# main.net
KiCad netlist of a schematic drawn in Altium Designer
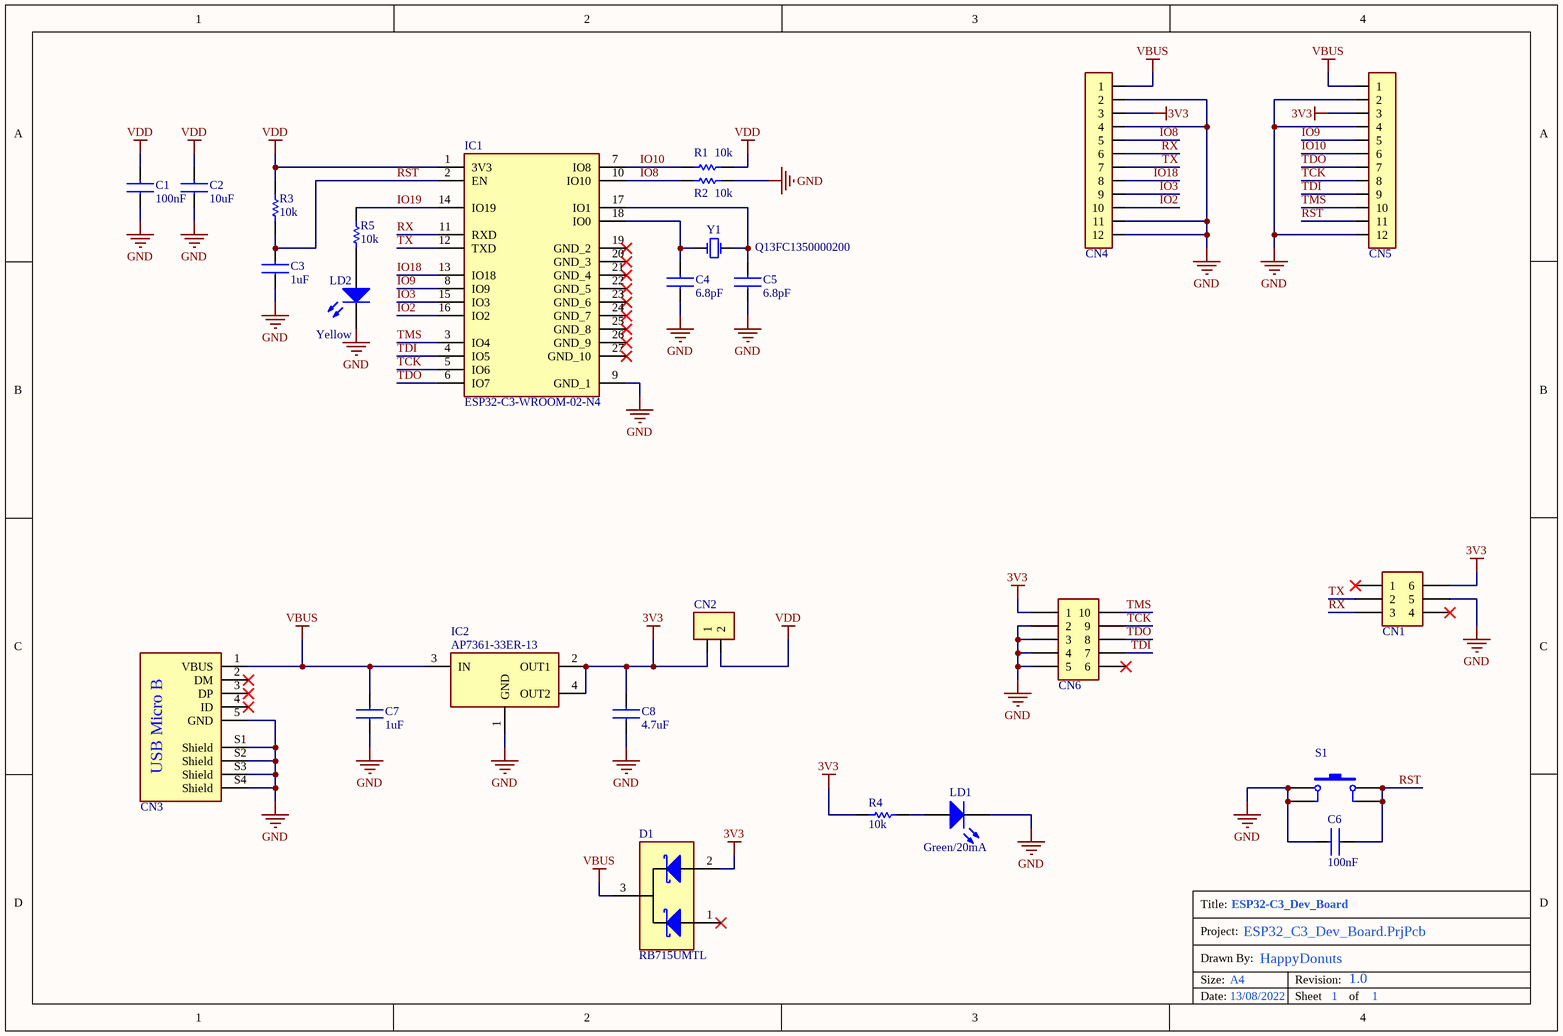
[diagram p0: main.SchDoc]

(export (version "E")
  (design (tool "Eeschema 10.0.6"))
  (components
    (comp (ref "C1")
      (value "100nF")
      (footprint "PcbLib1:CAPC2012X94N")
      (description "Capacitor")
      (fields
        (field (name "MANUFACTURER_PART_NUMBER") "CL21B104KBCNNNC")
        (field (name "MOUSER PART NUMBER") "187-CL21B104KBCNNNC")
      )
      (libsource (lib "Schlib1") (part "CL21B104KBCNNNC"))
    )
    (comp (ref "C2")
      (value "10uF")
      (footprint "PcbLib1:CAPC2012X135N")
      (description "Capacitor")
      (fields
        (field (name "MANUFACTURER_PART_NUMBER") "CL21A106MQFNNNE")
        (field (name "MOUSER PART NUMBER") "187-CL21A106MQFNNNE")
      )
      (libsource (lib "Schlib1") (part "CL21A106MQFNNNE"))
    )
    (comp (ref "C3")
      (value "1uF")
      (footprint "PcbLib1:CAPC2012X135N")
      (description "Capacitor")
      (fields
        (field (name "MANUFACTURER_PART_NUMBER") "CL21B105KBFNNNE")
        (field (name "MOUSER PART NUMBER") "187-CL21B105KBFNNNE")
      )
      (libsource (lib "Schlib1") (part "CL21B105KBFNNNE"))
    )
    (comp (ref "C4")
      (value "6.8pF")
      (footprint "PcbLib1:CAPC2012X94N")
      (description "Capacitor")
      (fields
        (field (name "MANUFACTURER_PART_NUMBER") "CC0805CRNPO9BN6R8")
        (field (name "MOUSER PART NUMBER") "603-CC805CRNPO9BN6R8")
      )
      (libsource (lib "Schlib1") (part "CC0805CRNPO9BN6R8"))
    )
    (comp (ref "C5")
      (value "6.8pF")
      (footprint "PcbLib1:CAPC2012X94N")
      (description "Capacitor")
      (fields
        (field (name "MANUFACTURER_PART_NUMBER") "CC0805CRNPO9BN6R8")
        (field (name "MOUSER PART NUMBER") "603-CC805CRNPO9BN6R8")
      )
      (libsource (lib "Schlib1") (part "CC0805CRNPO9BN6R8"))
    )
    (comp (ref "C6")
      (value "100nF")
      (footprint "PcbLib1:CAPC2012X94N")
      (description "Capacitor")
      (fields
        (field (name "MANUFACTURER_PART_NUMBER") "CL21B104KBCNNNC")
        (field (name "MOUSER PART NUMBER") "187-CL21B104KBCNNNC")
      )
      (libsource (lib "Schlib1") (part "CL21B104KBCNNNC"))
    )
    (comp (ref "C7")
      (value "1uF")
      (footprint "PcbLib1:CAPC2012X135N")
      (description "Capacitor")
      (fields
        (field (name "MANUFACTURER_PART_NUMBER") "CL21B105KBFNNNE")
        (field (name "MOUSER PART NUMBER") "187-CL21B105KBFNNNE")
      )
      (libsource (lib "Schlib1") (part "CL21B105KBFNNNE"))
    )
    (comp (ref "C8")
      (value "4.7uF")
      (footprint "PcbLib1:CAPC2012X135N")
      (description "Capacitor")
      (fields
        (field (name "MANUFACTURER_PART_NUMBER") "CL21A475KBQNNNE")
        (field (name "MOUSER PART NUMBER") "187-CL21A475KBQNNNE")
      )
      (libsource (lib "Schlib1") (part "CL21A475KBQNNNE"))
    )
    (comp (ref "CN1")
      (value "CN_2X3_1.27_BOX_1")
      (footprint "PcbLib1:CN_2X3_1.27_BOX_TH")
      (description "Connector")
      (libsource (lib "Schlib1") (part "CN_2X3_1.27_BOX_1"))
    )
    (comp (ref "CN2")
      (value "CN_2PIN")
      (footprint "PcbLib1:CN_2PIN")
      (description "Connector")
      (libsource (lib "Schlib1") (part "CN_2PIN"))
    )
    (comp (ref "CN3")
      (value "USB_B_AE")
      (footprint "PcbLib1:USB_B_AE")
      (description "USB connector")
      (libsource (lib "Schlib1") (part "USB_B_AE"))
    )
    (comp (ref "CN4")
      (value "CN_12PIN")
      (footprint "PcbLib1:CN_12PIN")
      (description "Connector")
      (libsource (lib "Schlib1") (part "CN_12PIN"))
    )
    (comp (ref "CN5")
      (value "CN_12PIN")
      (footprint "PcbLib1:CN_12PIN")
      (description "Connector")
      (libsource (lib "") (part "CN_12PIN_1"))
    )
    (comp (ref "CN6")
      (value "CN_2X5_1.27_BOX")
      (footprint "PcbLib1:CN_2X5_1.27_BOX_TH")
      (description "Connector")
      (libsource (lib "Schlib1") (part "CN_2X5_1.27_BOX"))
    )
    (comp (ref "D1")
      (value "RB715UMTL")
      (footprint "PcbLib1:DAN217UMTL")
      (description "Schottky Diode")
      (fields (field (name "MOUSER PART NUMBER") "755-RB715UMTL"))
      (libsource (lib "Schlib1") (part "RB715UMTL"))
    )
    (comp (ref "IC1")
      (value "ESP32-C3-WROOM-02-N4")
      (footprint "PcbLib1:ESP32C3WROOM02N4")
      (description "Integrated Circuit")
      (fields (field (name "MOUSER PART NUMBER") "356-ESP32C3WROOM02N4"))
      (libsource (lib "Schlib1") (part "ESP32-C3-WROOM-02-N4"))
    )
    (comp (ref "IC2")
      (value "AP7361-33ER-13")
      (footprint "PcbLib1:SOT230P700X180-4N")
      (description "LDO")
      (fields (field (name "MOUSER PART NUMBER") "621-AP7361-33ER-13"))
      (libsource (lib "Schlib1") (part "AP7361-33ER-13"))
    )
    (comp (ref "LD1")
      (value "Green/20mA")
      (footprint "PcbLib1:LEDC2012X85N_G")
      (description "LED")
      (fields
        (field (name "MANUFACTURER_PART_NUMBER") "LTST-C171KGKT")
        (field (name "MOUSER PART NUMBER") "859-LTST-C171KGKT")
      )
      (libsource (lib "Schlib1") (part "LTST-C171KGKT"))
    )
    (comp (ref "LD2")
      (value "Yellow")
      (footprint "PcbLib1:LEDC2012X85N_Y")
      (description "LED")
      (fields
        (field (name "MANUFACTURER_PART_NUMBER") "LTST-C171KSKT")
        (field (name "MOUSER PART NUMBER") "859-LTST-C171KSKT")
      )
      (libsource (lib "Schlib1") (part "LTST-C171KSKT"))
    )
    (comp (ref "R1")
      (value "10k")
      (footprint "PcbLib1:RESC2012X60N")
      (description "Resistor")
      (fields
        (field (name "MANUFACTURER_PART_NUMBER") "RC0805FR-0710KL")
        (field (name "MOUSER PART NUMBER") "603-RC0805FR-0710KL")
      )
      (libsource (lib "Schlib1") (part "RC0805FR-0710KL"))
    )
    (comp (ref "R2")
      (value "10k")
      (footprint "PcbLib1:RESC2012X60N")
      (description "Resistor")
      (fields
        (field (name "MANUFACTURER_PART_NUMBER") "RC0805FR-0710KL")
        (field (name "MOUSER PART NUMBER") "603-RC0805FR-0710KL")
      )
      (libsource (lib "Schlib1") (part "RC0805FR-0710KL"))
    )
    (comp (ref "R3")
      (value "10k")
      (footprint "PcbLib1:RESC2012X60N")
      (description "Resistor")
      (fields
        (field (name "MANUFACTURER_PART_NUMBER") "RC0805FR-0710KL")
        (field (name "MOUSER PART NUMBER") "603-RC0805FR-0710KL")
      )
      (libsource (lib "Schlib1") (part "RC0805FR-0710KL"))
    )
    (comp (ref "R4")
      (value "10k")
      (footprint "PcbLib1:RESC2012X60N")
      (description "Resistor")
      (fields
        (field (name "MANUFACTURER_PART_NUMBER") "RC0805FR-0710KL")
        (field (name "MOUSER PART NUMBER") "603-RC0805FR-0710KL")
      )
      (libsource (lib "Schlib1") (part "RC0805FR-0710KL"))
    )
    (comp (ref "R5")
      (value "10k")
      (footprint "PcbLib1:RESC2012X60N")
      (description "Resistor")
      (fields
        (field (name "MANUFACTURER_PART_NUMBER") "RC0805FR-0710KL")
        (field (name "MOUSER PART NUMBER") "603-RC0805FR-0710KL")
      )
      (libsource (lib "Schlib1") (part "RC0805FR-0710KL"))
    )
    (comp (ref "S1")
      (value "SKRPABE010")
      (footprint "PcbLib1:PTS815SJM250SMTRLFS")
      (description "Switch")
      (fields (field (name "MOUSER PART NUMBER") "688-SKRPAB"))
      (libsource (lib "Schlib1") (part "SKRPABE010"))
    )
    (comp (ref "Y1")
      (value "Q13FC1350000200")
      (footprint "PcbLib1:Q13FC1350000200")
      (description "Crystal")
      (libsource (lib "Schlib1") (part "Q13FC1350000200"))
    )
  )
  (nets
    (net (code "1") (name "/IO2") (class "Default")
      (node (ref "CN4") (pin "10") (pinfunction "10_10") (pintype "passive"))
      (node (ref "IC1") (pin "16") (pinfunction "IO2_16") (pintype "passive"))
    )
    (net (code "2") (name "/IO3") (class "Default")
      (node (ref "CN4") (pin "9") (pinfunction "9_9") (pintype "passive"))
      (node (ref "IC1") (pin "15") (pinfunction "IO3_15") (pintype "passive"))
    )
    (net (code "3") (name "/IO8") (class "Default")
      (node (ref "CN4") (pin "5") (pinfunction "5_5") (pintype "passive"))
      (node (ref "IC1") (pin "10") (pinfunction "IO10_10") (pintype "passive"))
      (node (ref "R2") (pin "1") (pinfunction "1_1") (pintype "passive"))
    )
    (net (code "4") (name "/IO9") (class "Default")
      (node (ref "CN5") (pin "5") (pinfunction "5_5") (pintype "passive"))
      (node (ref "IC1") (pin "8") (pinfunction "IO9_8") (pintype "passive"))
    )
    (net (code "5") (name "/IO10") (class "Default")
      (node (ref "CN5") (pin "6") (pinfunction "6_6") (pintype "passive"))
      (node (ref "IC1") (pin "7") (pinfunction "IO8_7") (pintype "passive"))
      (node (ref "R1") (pin "2") (pinfunction "2_2") (pintype "passive"))
    )
    (net (code "6") (name "/IO18") (class "Default")
      (node (ref "CN4") (pin "8") (pinfunction "8_8") (pintype "passive"))
      (node (ref "IC1") (pin "13") (pinfunction "IO18_13") (pintype "passive"))
    )
    (net (code "7") (name "/IO19") (class "Default")
      (node (ref "IC1") (pin "14") (pinfunction "IO19_14") (pintype "passive"))
      (node (ref "R5") (pin "2") (pinfunction "2_2") (pintype "passive"))
    )
    (net (code "8") (name "/RST") (class "Default")
      (node (ref "C3") (pin "2") (pinfunction "2_2") (pintype "passive"))
      (node (ref "C6") (pin "2") (pinfunction "2_2") (pintype "passive"))
      (node (ref "CN5") (pin "11") (pinfunction "11_11") (pintype "passive"))
      (node (ref "IC1") (pin "2") (pinfunction "EN_2") (pintype "passive"))
      (node (ref "R3") (pin "1") (pinfunction "1_1") (pintype "passive"))
      (node (ref "S1") (pin "3") (pinfunction "3_3") (pintype "passive"))
      (node (ref "S1") (pin "4") (pinfunction "4_4") (pintype "passive"))
    )
    (net (code "9") (name "/RX") (class "Default")
      (node (ref "CN1") (pin "3") (pinfunction "3_3") (pintype "passive"))
      (node (ref "CN4") (pin "6") (pinfunction "6_6") (pintype "passive"))
      (node (ref "IC1") (pin "11") (pinfunction "RXD_11") (pintype "passive"))
    )
    (net (code "10") (name "/TCK") (class "Default")
      (node (ref "CN5") (pin "8") (pinfunction "8_8") (pintype "passive"))
      (node (ref "CN6") (pin "9") (pinfunction "9_9") (pintype "passive"))
      (node (ref "IC1") (pin "5") (pinfunction "IO6_5") (pintype "passive"))
    )
    (net (code "11") (name "/TDI") (class "Default")
      (node (ref "CN5") (pin "9") (pinfunction "9_9") (pintype "passive"))
      (node (ref "CN6") (pin "7") (pinfunction "7_7") (pintype "passive"))
      (node (ref "IC1") (pin "4") (pinfunction "IO5_4") (pintype "passive"))
    )
    (net (code "12") (name "/TDO") (class "Default")
      (node (ref "CN5") (pin "7") (pinfunction "7_7") (pintype "passive"))
      (node (ref "CN6") (pin "8") (pinfunction "8_8") (pintype "passive"))
      (node (ref "IC1") (pin "6") (pinfunction "IO7_6") (pintype "passive"))
    )
    (net (code "13") (name "/TMS") (class "Default")
      (node (ref "CN5") (pin "10") (pinfunction "10_10") (pintype "passive"))
      (node (ref "CN6") (pin "10") (pinfunction "10_10") (pintype "passive"))
      (node (ref "IC1") (pin "3") (pinfunction "IO4_3") (pintype "passive"))
    )
    (net (code "14") (name "/TX") (class "Default")
      (node (ref "CN1") (pin "2") (pinfunction "2_2") (pintype "passive"))
      (node (ref "CN4") (pin "7") (pinfunction "7_7") (pintype "passive"))
      (node (ref "IC1") (pin "12") (pinfunction "TXD_12") (pintype "passive"))
    )
    (net (code "15") (name "3V3") (class "Default")
      (node (ref "C8") (pin "2") (pinfunction "2_2") (pintype "passive"))
      (node (ref "CN1") (pin "6") (pinfunction "6_6") (pintype "passive"))
      (node (ref "CN2") (pin "1") (pinfunction "1_1") (pintype "passive"))
      (node (ref "CN4") (pin "3") (pinfunction "3_3") (pintype "passive"))
      (node (ref "CN5") (pin "3") (pinfunction "3_3") (pintype "passive"))
      (node (ref "CN6") (pin "1") (pinfunction "1_1") (pintype "passive"))
      (node (ref "D1") (pin "2") (pinfunction "K_2_2") (pintype "passive"))
      (node (ref "IC2") (pin "2") (pinfunction "OUT1_2") (pintype "passive"))
      (node (ref "IC2") (pin "4") (pinfunction "OUT2_4") (pintype "passive"))
      (node (ref "R4") (pin "1") (pinfunction "1_1") (pintype "passive"))
    )
    (net (code "16") (name "GND") (class "Default")
      (node (ref "C1") (pin "1") (pinfunction "1_1") (pintype "passive"))
      (node (ref "C2") (pin "1") (pinfunction "1_1") (pintype "passive"))
      (node (ref "C3") (pin "1") (pinfunction "1_1") (pintype "passive"))
      (node (ref "C4") (pin "1") (pinfunction "1_1") (pintype "passive"))
      (node (ref "C5") (pin "1") (pinfunction "1_1") (pintype "passive"))
      (node (ref "C6") (pin "1") (pinfunction "1_1") (pintype "passive"))
      (node (ref "C7") (pin "1") (pinfunction "1_1") (pintype "passive"))
      (node (ref "C8") (pin "1") (pinfunction "1_1") (pintype "passive"))
      (node (ref "CN1") (pin "5") (pinfunction "5_5") (pintype "passive"))
      (node (ref "CN3") (pin "5") (pinfunction "GND_5") (pintype "passive"))
      (node (ref "CN3") (pin "S1") (pinfunction "Shield_S1") (pintype "passive"))
      (node (ref "CN3") (pin "S2") (pinfunction "Shield_S2") (pintype "passive"))
      (node (ref "CN3") (pin "S3") (pinfunction "Shield_S3") (pintype "passive"))
      (node (ref "CN3") (pin "S4") (pinfunction "Shield_S4") (pintype "passive"))
      (node (ref "CN4") (pin "11") (pinfunction "11_11") (pintype "passive"))
      (node (ref "CN4") (pin "12") (pinfunction "12_12") (pintype "passive"))
      (node (ref "CN4") (pin "2") (pinfunction "2_2") (pintype "passive"))
      (node (ref "CN4") (pin "4") (pinfunction "4_4") (pintype "passive"))
      (node (ref "CN5") (pin "12") (pinfunction "12_12") (pintype "passive"))
      (node (ref "CN5") (pin "2") (pinfunction "2_2") (pintype "passive"))
      (node (ref "CN5") (pin "4") (pinfunction "4_4") (pintype "passive"))
      (node (ref "CN6") (pin "2") (pinfunction "2_2") (pintype "passive"))
      (node (ref "CN6") (pin "3") (pinfunction "3_3") (pintype "passive"))
      (node (ref "CN6") (pin "4") (pinfunction "4_4") (pintype "passive"))
      (node (ref "CN6") (pin "5") (pinfunction "5_5") (pintype "passive"))
      (node (ref "IC1") (pin "9") (pinfunction "GND_1_9") (pintype "passive"))
      (node (ref "IC2") (pin "1") (pinfunction "GND_1") (pintype "passive"))
      (node (ref "LD1") (pin "1") (pinfunction "K_1") (pintype "passive"))
      (node (ref "LD2") (pin "1") (pinfunction "K_1") (pintype "passive"))
      (node (ref "R2") (pin "2") (pinfunction "2_2") (pintype "passive"))
      (node (ref "S1") (pin "1") (pinfunction "1_1") (pintype "passive"))
      (node (ref "S1") (pin "2") (pinfunction "2_2") (pintype "passive"))
    )
    (net (code "17") (name "Net-(IC1-IO0)") (class "Default")
      (node (ref "C4") (pin "2") (pinfunction "2_2") (pintype "passive"))
      (node (ref "IC1") (pin "18") (pinfunction "IO0_18") (pintype "passive"))
      (node (ref "Y1") (pin "1") (pinfunction "1_1") (pintype "passive"))
    )
    (net (code "18") (name "Net-(IC1-IO1)") (class "Default")
      (node (ref "C5") (pin "2") (pinfunction "2_2") (pintype "passive"))
      (node (ref "IC1") (pin "17") (pinfunction "IO1_17") (pintype "passive"))
      (node (ref "Y1") (pin "2") (pinfunction "2_2") (pintype "passive"))
    )
    (net (code "19") (name "Net-(LD1-A)") (class "Default")
      (node (ref "LD1") (pin "2") (pinfunction "A_2") (pintype "passive"))
      (node (ref "R4") (pin "2") (pinfunction "2_2") (pintype "passive"))
    )
    (net (code "20") (name "Net-(LD2-A)") (class "Default")
      (node (ref "LD2") (pin "2") (pinfunction "A_2") (pintype "passive"))
      (node (ref "R5") (pin "1") (pinfunction "1_1") (pintype "passive"))
    )
    (net (code "21") (name "VBUS") (class "Default")
      (node (ref "C7") (pin "2") (pinfunction "2_2") (pintype "passive"))
      (node (ref "CN3") (pin "1") (pinfunction "VBUS_1") (pintype "passive"))
      (node (ref "CN4") (pin "1") (pinfunction "1_1") (pintype "passive"))
      (node (ref "CN5") (pin "1") (pinfunction "1_1") (pintype "passive"))
      (node (ref "D1") (pin "3") (pinfunction "COM_A_3") (pintype "passive"))
      (node (ref "IC2") (pin "3") (pinfunction "IN_3") (pintype "passive"))
    )
    (net (code "22") (name "VDD") (class "Default")
      (node (ref "C1") (pin "2") (pinfunction "2_2") (pintype "passive"))
      (node (ref "C2") (pin "2") (pinfunction "2_2") (pintype "passive"))
      (node (ref "CN2") (pin "2") (pinfunction "2_2") (pintype "passive"))
      (node (ref "IC1") (pin "1") (pinfunction "3V3_1") (pintype "passive"))
      (node (ref "R1") (pin "1") (pinfunction "1_1") (pintype "passive"))
      (node (ref "R3") (pin "2") (pinfunction "2_2") (pintype "passive"))
    )
    (net (code "23") (name "unconnected-(CN1-Pad1)") (class "Default")
      (node (ref "CN1") (pin "1") (pinfunction "1_1") (pintype "passive+no_connect"))
    )
    (net (code "24") (name "unconnected-(CN1-Pad4)") (class "Default")
      (node (ref "CN1") (pin "4") (pinfunction "4_4") (pintype "passive+no_connect"))
    )
    (net (code "25") (name "unconnected-(CN3-DM-Pad2)") (class "Default")
      (node (ref "CN3") (pin "2") (pinfunction "DM_2") (pintype "passive+no_connect"))
    )
    (net (code "26") (name "unconnected-(CN3-DP-Pad3)") (class "Default")
      (node (ref "CN3") (pin "3") (pinfunction "DP_3") (pintype "passive+no_connect"))
    )
    (net (code "27") (name "unconnected-(CN3-ID-Pad4)") (class "Default")
      (node (ref "CN3") (pin "4") (pinfunction "ID_4") (pintype "passive+no_connect"))
    )
    (net (code "28") (name "unconnected-(CN6-Pad6)") (class "Default")
      (node (ref "CN6") (pin "6") (pinfunction "6_6") (pintype "passive+no_connect"))
    )
    (net (code "29") (name "unconnected-(D1-K_1-Pad1)") (class "Default")
      (node (ref "D1") (pin "1") (pinfunction "K_1_1") (pintype "passive+no_connect"))
    )
    (net (code "30") (name "unconnected-(IC1-GND_2-Pad19)") (class "Default")
      (node (ref "IC1") (pin "19") (pinfunction "GND_2_19") (pintype "passive+no_connect"))
    )
    (net (code "31") (name "unconnected-(IC1-GND_3-Pad20)") (class "Default")
      (node (ref "IC1") (pin "20") (pinfunction "GND_3_20") (pintype "passive+no_connect"))
    )
    (net (code "32") (name "unconnected-(IC1-GND_4-Pad21)") (class "Default")
      (node (ref "IC1") (pin "21") (pinfunction "GND_4_21") (pintype "passive+no_connect"))
    )
    (net (code "33") (name "unconnected-(IC1-GND_5-Pad22)") (class "Default")
      (node (ref "IC1") (pin "22") (pinfunction "GND_5_22") (pintype "passive+no_connect"))
    )
    (net (code "34") (name "unconnected-(IC1-GND_6-Pad23)") (class "Default")
      (node (ref "IC1") (pin "23") (pinfunction "GND_6_23") (pintype "passive+no_connect"))
    )
    (net (code "35") (name "unconnected-(IC1-GND_7-Pad24)") (class "Default")
      (node (ref "IC1") (pin "24") (pinfunction "GND_7_24") (pintype "passive+no_connect"))
    )
    (net (code "36") (name "unconnected-(IC1-GND_8-Pad25)") (class "Default")
      (node (ref "IC1") (pin "25") (pinfunction "GND_8_25") (pintype "passive+no_connect"))
    )
    (net (code "37") (name "unconnected-(IC1-GND_9-Pad26)") (class "Default")
      (node (ref "IC1") (pin "26") (pinfunction "GND_9_26") (pintype "passive+no_connect"))
    )
    (net (code "38") (name "unconnected-(IC1-GND_10-Pad27)") (class "Default")
      (node (ref "IC1") (pin "27") (pinfunction "GND_10_27") (pintype "passive+no_connect"))
    )
  )
)
